# SleepLiteRev3.net
KiCad netlist of a schematic drawn in EAGLE
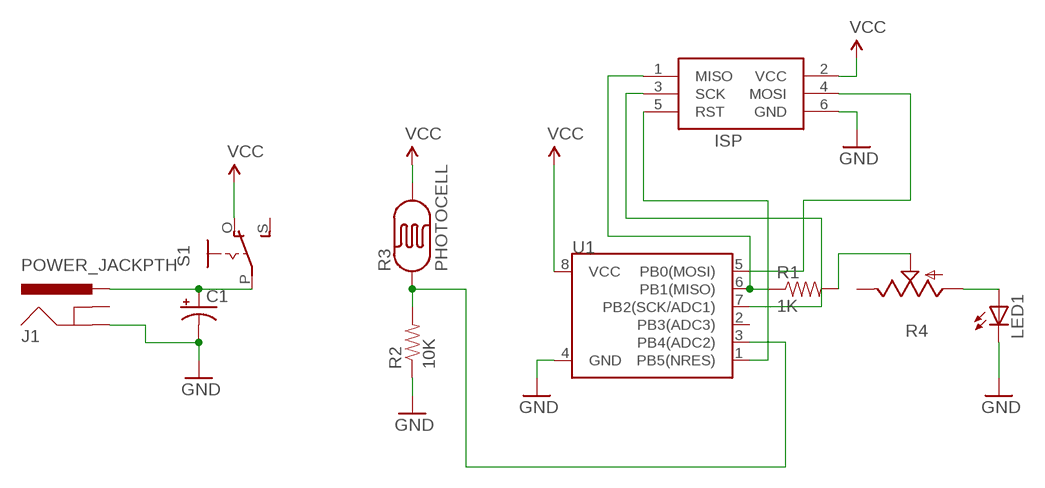
[diagram p0: schematic, sheet 1]

(export (version "E")
  (design (tool "Eeschema 10.0.6"))
  (components
    (comp (ref "C1")
      (value "CAP_POLPTH2")
      (footprint "eagle-import:CPOL-RADIAL-10UF-25V")
      (libsource (lib "eagle-import") (part "CAP_POLPTH2"))
    )
    (comp (ref "ISP")
      (value "AVRISP-6")
      (footprint "eagle-import:AVRISP")
      (libsource (lib "eagle-import") (part "AVRISP-6"))
    )
    (comp (ref "J1")
      (value "POWER_JACKPTH")
      (footprint "eagle-import:POWER_JACK_PTH")
      (libsource (lib "eagle-import") (part "POWER_JACKPTH"))
    )
    (comp (ref "LED1")
      (value "LED5MM")
      (footprint "eagle-import:LED5MM")
      (libsource (lib "eagle-import") (part "LED5MM"))
    )
    (comp (ref "R1")
      (value "1K")
      (footprint "eagle-import:AXIAL-0.4")
      (libsource (lib "eagle-import") (part "RESISTORPTH-1/4W"))
    )
    (comp (ref "R2")
      (value "10K")
      (footprint "eagle-import:AXIAL-0.4")
      (libsource (lib "eagle-import") (part "RESISTORPTH-1/4W"))
    )
    (comp (ref "R3")
      (value "PHOTOCELL")
      (footprint "eagle-import:PHOTOCELL-KIT")
      (libsource (lib "eagle-import") (part "PHOTOCELLPTH-KIT"))
    )
    (comp (ref "R4")
      (value "TRIM_US-B64Y")
      (footprint "eagle-import:B64Y")
      (libsource (lib "eagle-import") (part "TRIM_US-B64Y"))
    )
    (comp (ref "S1")
      (value "EG1218S")
      (footprint "eagle-import:EG1218")
      (libsource (lib "eagle-import") (part "EG1218S"))
    )
    (comp (ref "U1")
      (value "ATTINY13DIP")
      (footprint "eagle-import:DIP08")
      (libsource (lib "eagle-import") (part "ATTINY13DIP"))
    )
  )
  (nets
    (net (code "1") (name "GND") (class "Default")
      (node (ref "C1") (pin "2") (pinfunction "-_2") (pintype "passive"))
      (node (ref "ISP") (pin "6") (pinfunction "GND_6") (pintype "power_in"))
      (node (ref "J1") (pin "GND") (pinfunction "GND_GND") (pintype "bidirectional"))
      (node (ref "LED1") (pin "K") (pinfunction "C_K") (pintype "passive"))
      (node (ref "R2") (pin "P$1") (pinfunction "1_P$1") (pintype "passive"))
      (node (ref "U1") (pin "4") (pinfunction "GND_4") (pintype "bidirectional"))
    )
    (net (code "2") (name "Net-(C1-+)") (class "Default")
      (node (ref "C1") (pin "1") (pinfunction "+_1") (pintype "passive"))
      (node (ref "J1") (pin "PWR") (pinfunction "PWR_PWR") (pintype "bidirectional"))
      (node (ref "S1") (pin "P") (pinfunction "P_P") (pintype "passive"))
    )
    (net (code "3") (name "Net-(ISP-MISO)") (class "Default")
      (node (ref "ISP") (pin "1") (pinfunction "MISO_1") (pintype "input"))
      (node (ref "R1") (pin "P$1") (pinfunction "1_P$1") (pintype "passive"))
      (node (ref "U1") (pin "6") (pinfunction "PB1(MISO)_6") (pintype "bidirectional"))
    )
    (net (code "4") (name "Net-(ISP-MOSI)") (class "Default")
      (node (ref "ISP") (pin "4") (pinfunction "MOSI_4") (pintype "output"))
      (node (ref "U1") (pin "5") (pinfunction "PB0(MOSI)_5") (pintype "bidirectional"))
    )
    (net (code "5") (name "Net-(ISP-RST)") (class "Default")
      (node (ref "ISP") (pin "5") (pinfunction "RST_5") (pintype "output"))
      (node (ref "U1") (pin "1") (pinfunction "PB5(NRES)_1") (pintype "bidirectional"))
    )
    (net (code "6") (name "Net-(ISP-SCK)") (class "Default")
      (node (ref "ISP") (pin "3") (pinfunction "SCK_3") (pintype "output"))
      (node (ref "U1") (pin "7") (pinfunction "PB2(SCK/ADC1)_7") (pintype "bidirectional"))
    )
    (net (code "7") (name "Net-(LED1-PadA)") (class "Default")
      (node (ref "LED1") (pin "A") (pinfunction "A_A") (pintype "passive"))
      (node (ref "R4") (pin "A") (pinfunction "A_A") (pintype "passive"))
    )
    (net (code "8") (name "Net-(R1-2)") (class "Default")
      (node (ref "R1") (pin "P$2") (pinfunction "2_P$2") (pintype "passive"))
      (node (ref "R4") (pin "S") (pinfunction "S_S") (pintype "passive"))
    )
    (net (code "9") (name "Net-(R2-2)") (class "Default")
      (node (ref "R2") (pin "P$2") (pinfunction "2_P$2") (pintype "passive"))
      (node (ref "R3") (pin "1") (pinfunction "P$1_1") (pintype "bidirectional"))
      (node (ref "U1") (pin "3") (pinfunction "PB4(ADC2)_3") (pintype "bidirectional"))
    )
    (net (code "10") (name "VCC") (class "Default")
      (node (ref "ISP") (pin "2") (pinfunction "VCC_2") (pintype "power_in"))
      (node (ref "R3") (pin "2") (pinfunction "P$2_2") (pintype "bidirectional"))
      (node (ref "S1") (pin "O") (pinfunction "O_O") (pintype "passive"))
      (node (ref "U1") (pin "8") (pinfunction "VCC_8") (pintype "bidirectional"))
    )
    (net (code "11") (name "unconnected-(J1-PadGNDBREAK)") (class "Default")
      (node (ref "J1") (pin "GNDBREAK") (pinfunction "GNDBREAK_GNDBREAK") (pintype "bidirectional"))
    )
    (net (code "12") (name "unconnected-(R4-PadE)") (class "Default")
      (node (ref "R4") (pin "E") (pinfunction "E_E") (pintype "passive"))
    )
    (net (code "13") (name "unconnected-(S1-PadS)") (class "Default")
      (node (ref "S1") (pin "S") (pinfunction "S_S") (pintype "passive"))
    )
    (net (code "14") (name "unconnected-(U1-PB3(ADC3)-Pad2)") (class "Default")
      (node (ref "U1") (pin "2") (pinfunction "PB3(ADC3)_2") (pintype "bidirectional"))
    )
  )
)
